# 2024-SS-ZT-2.net
KiCad netlist of a schematic drawn in EasyEDA Pro
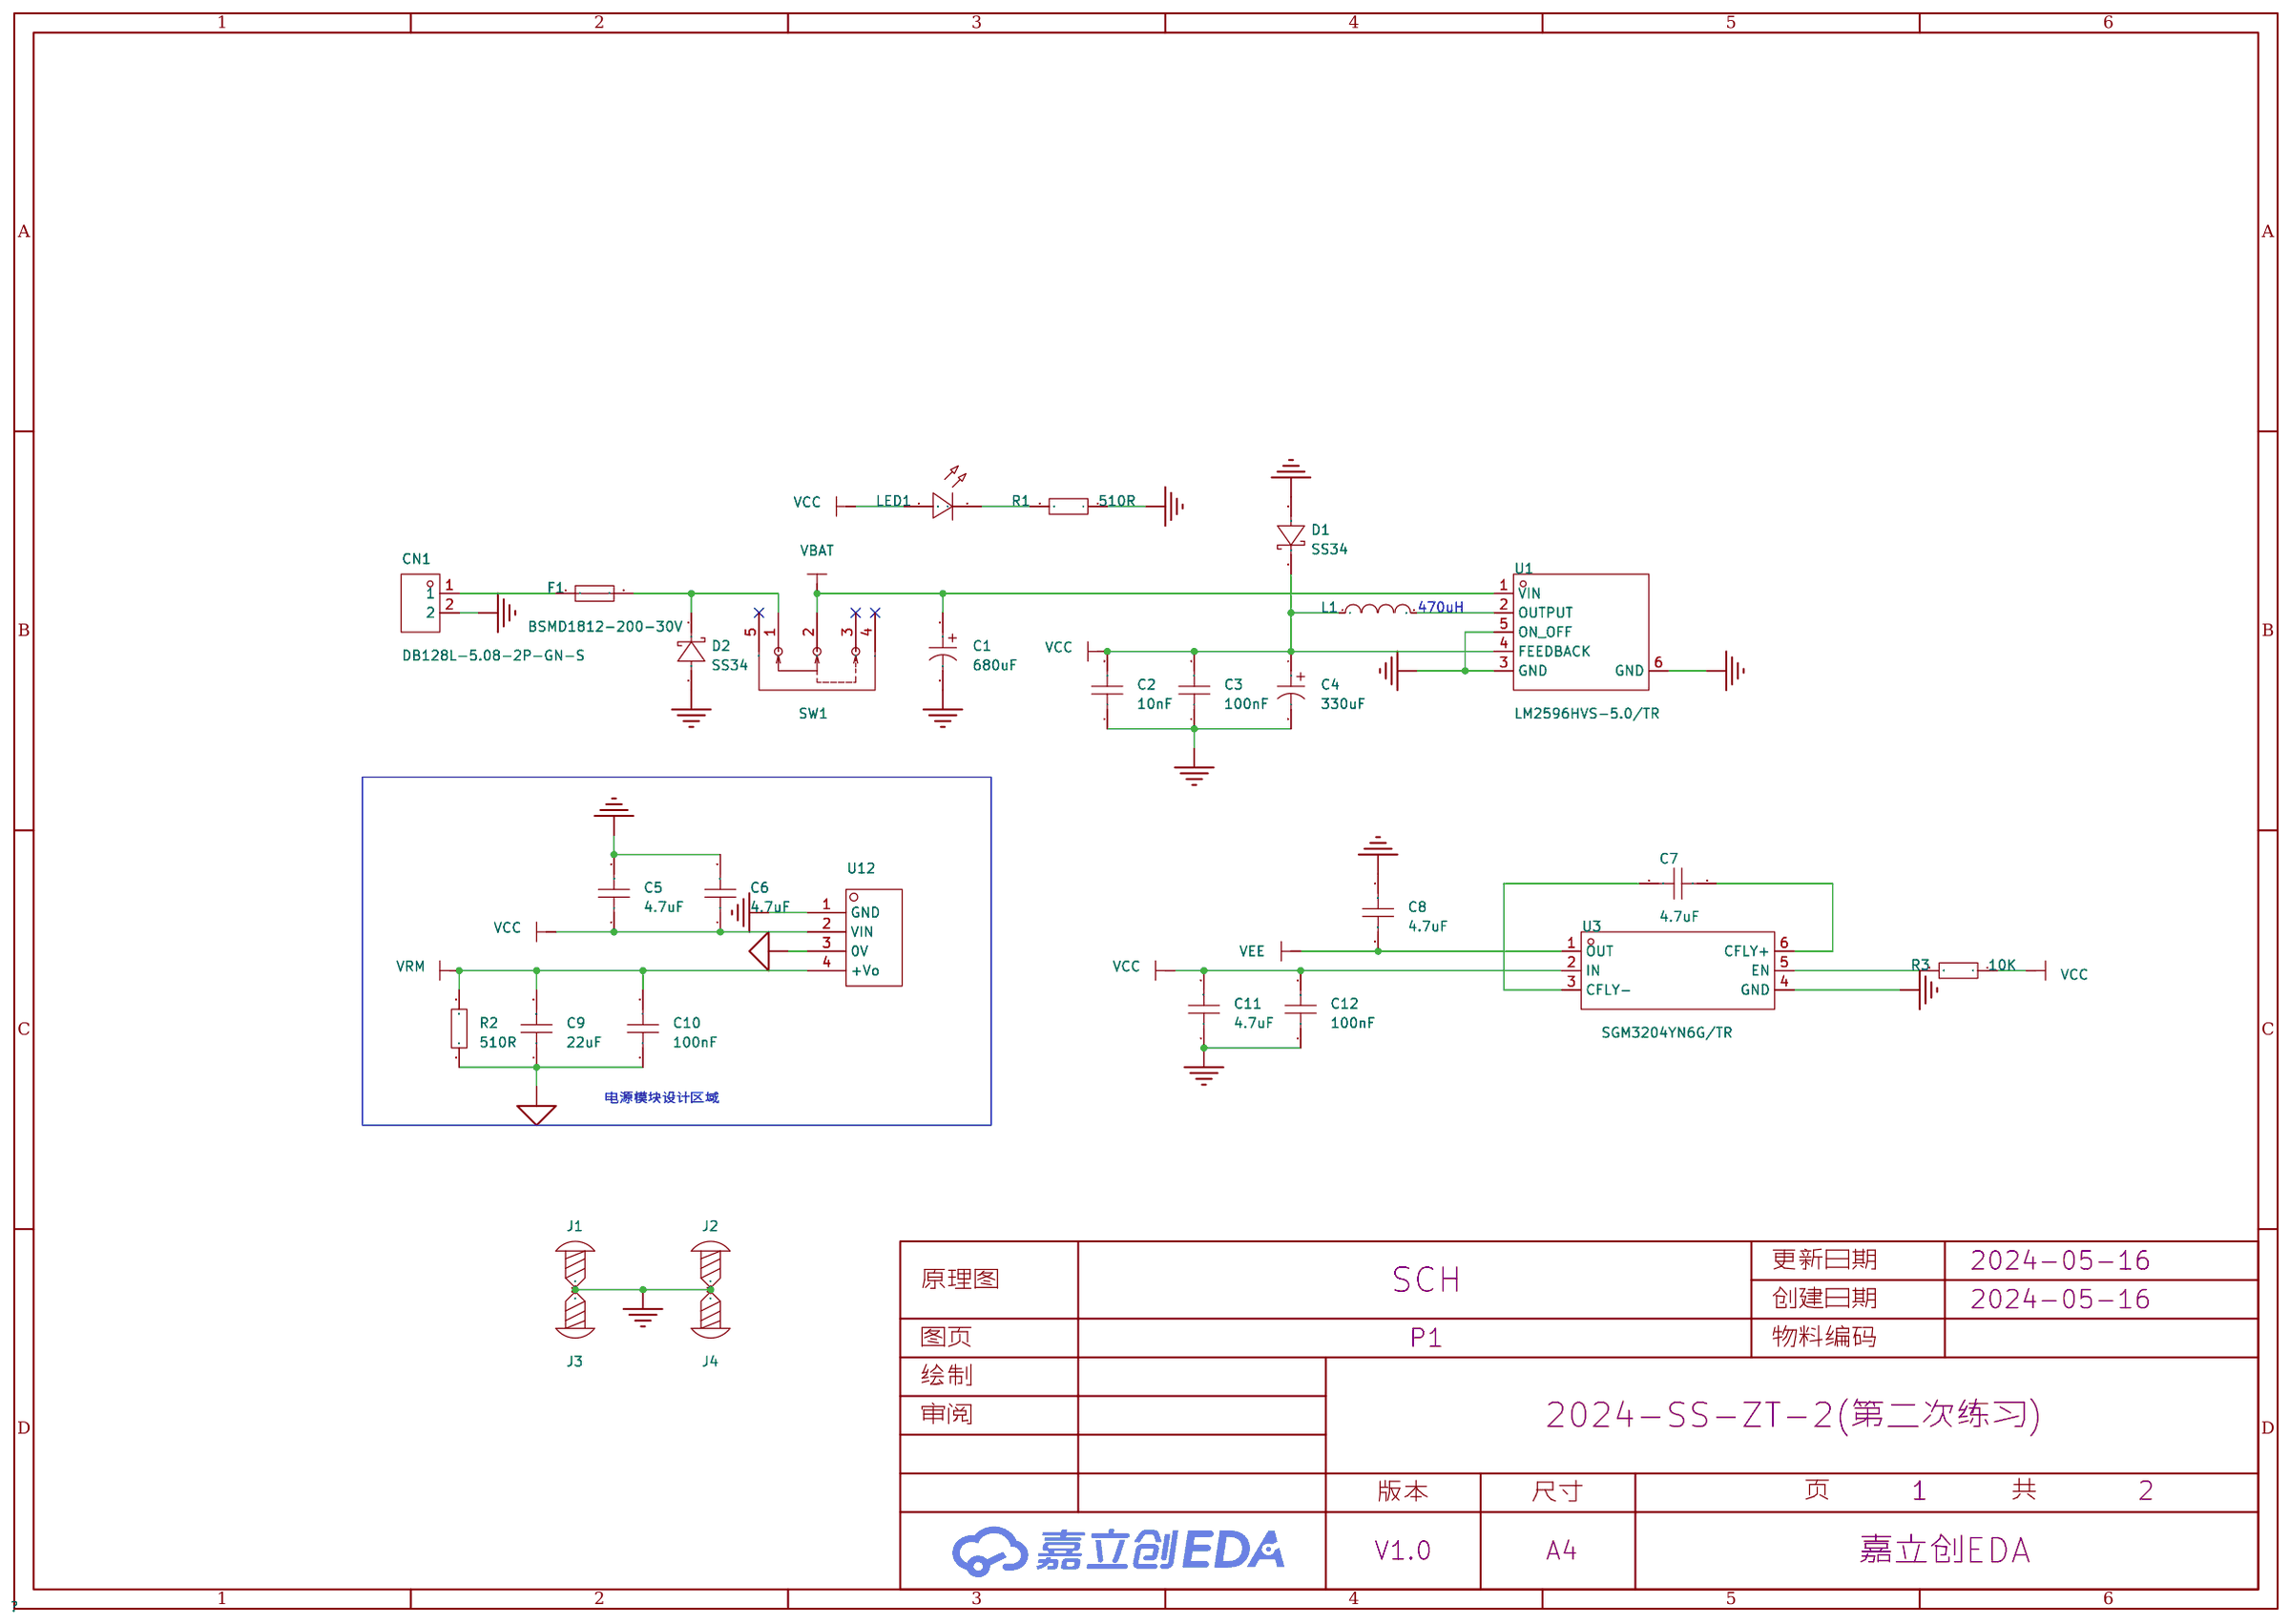
[diagram p0: P1]
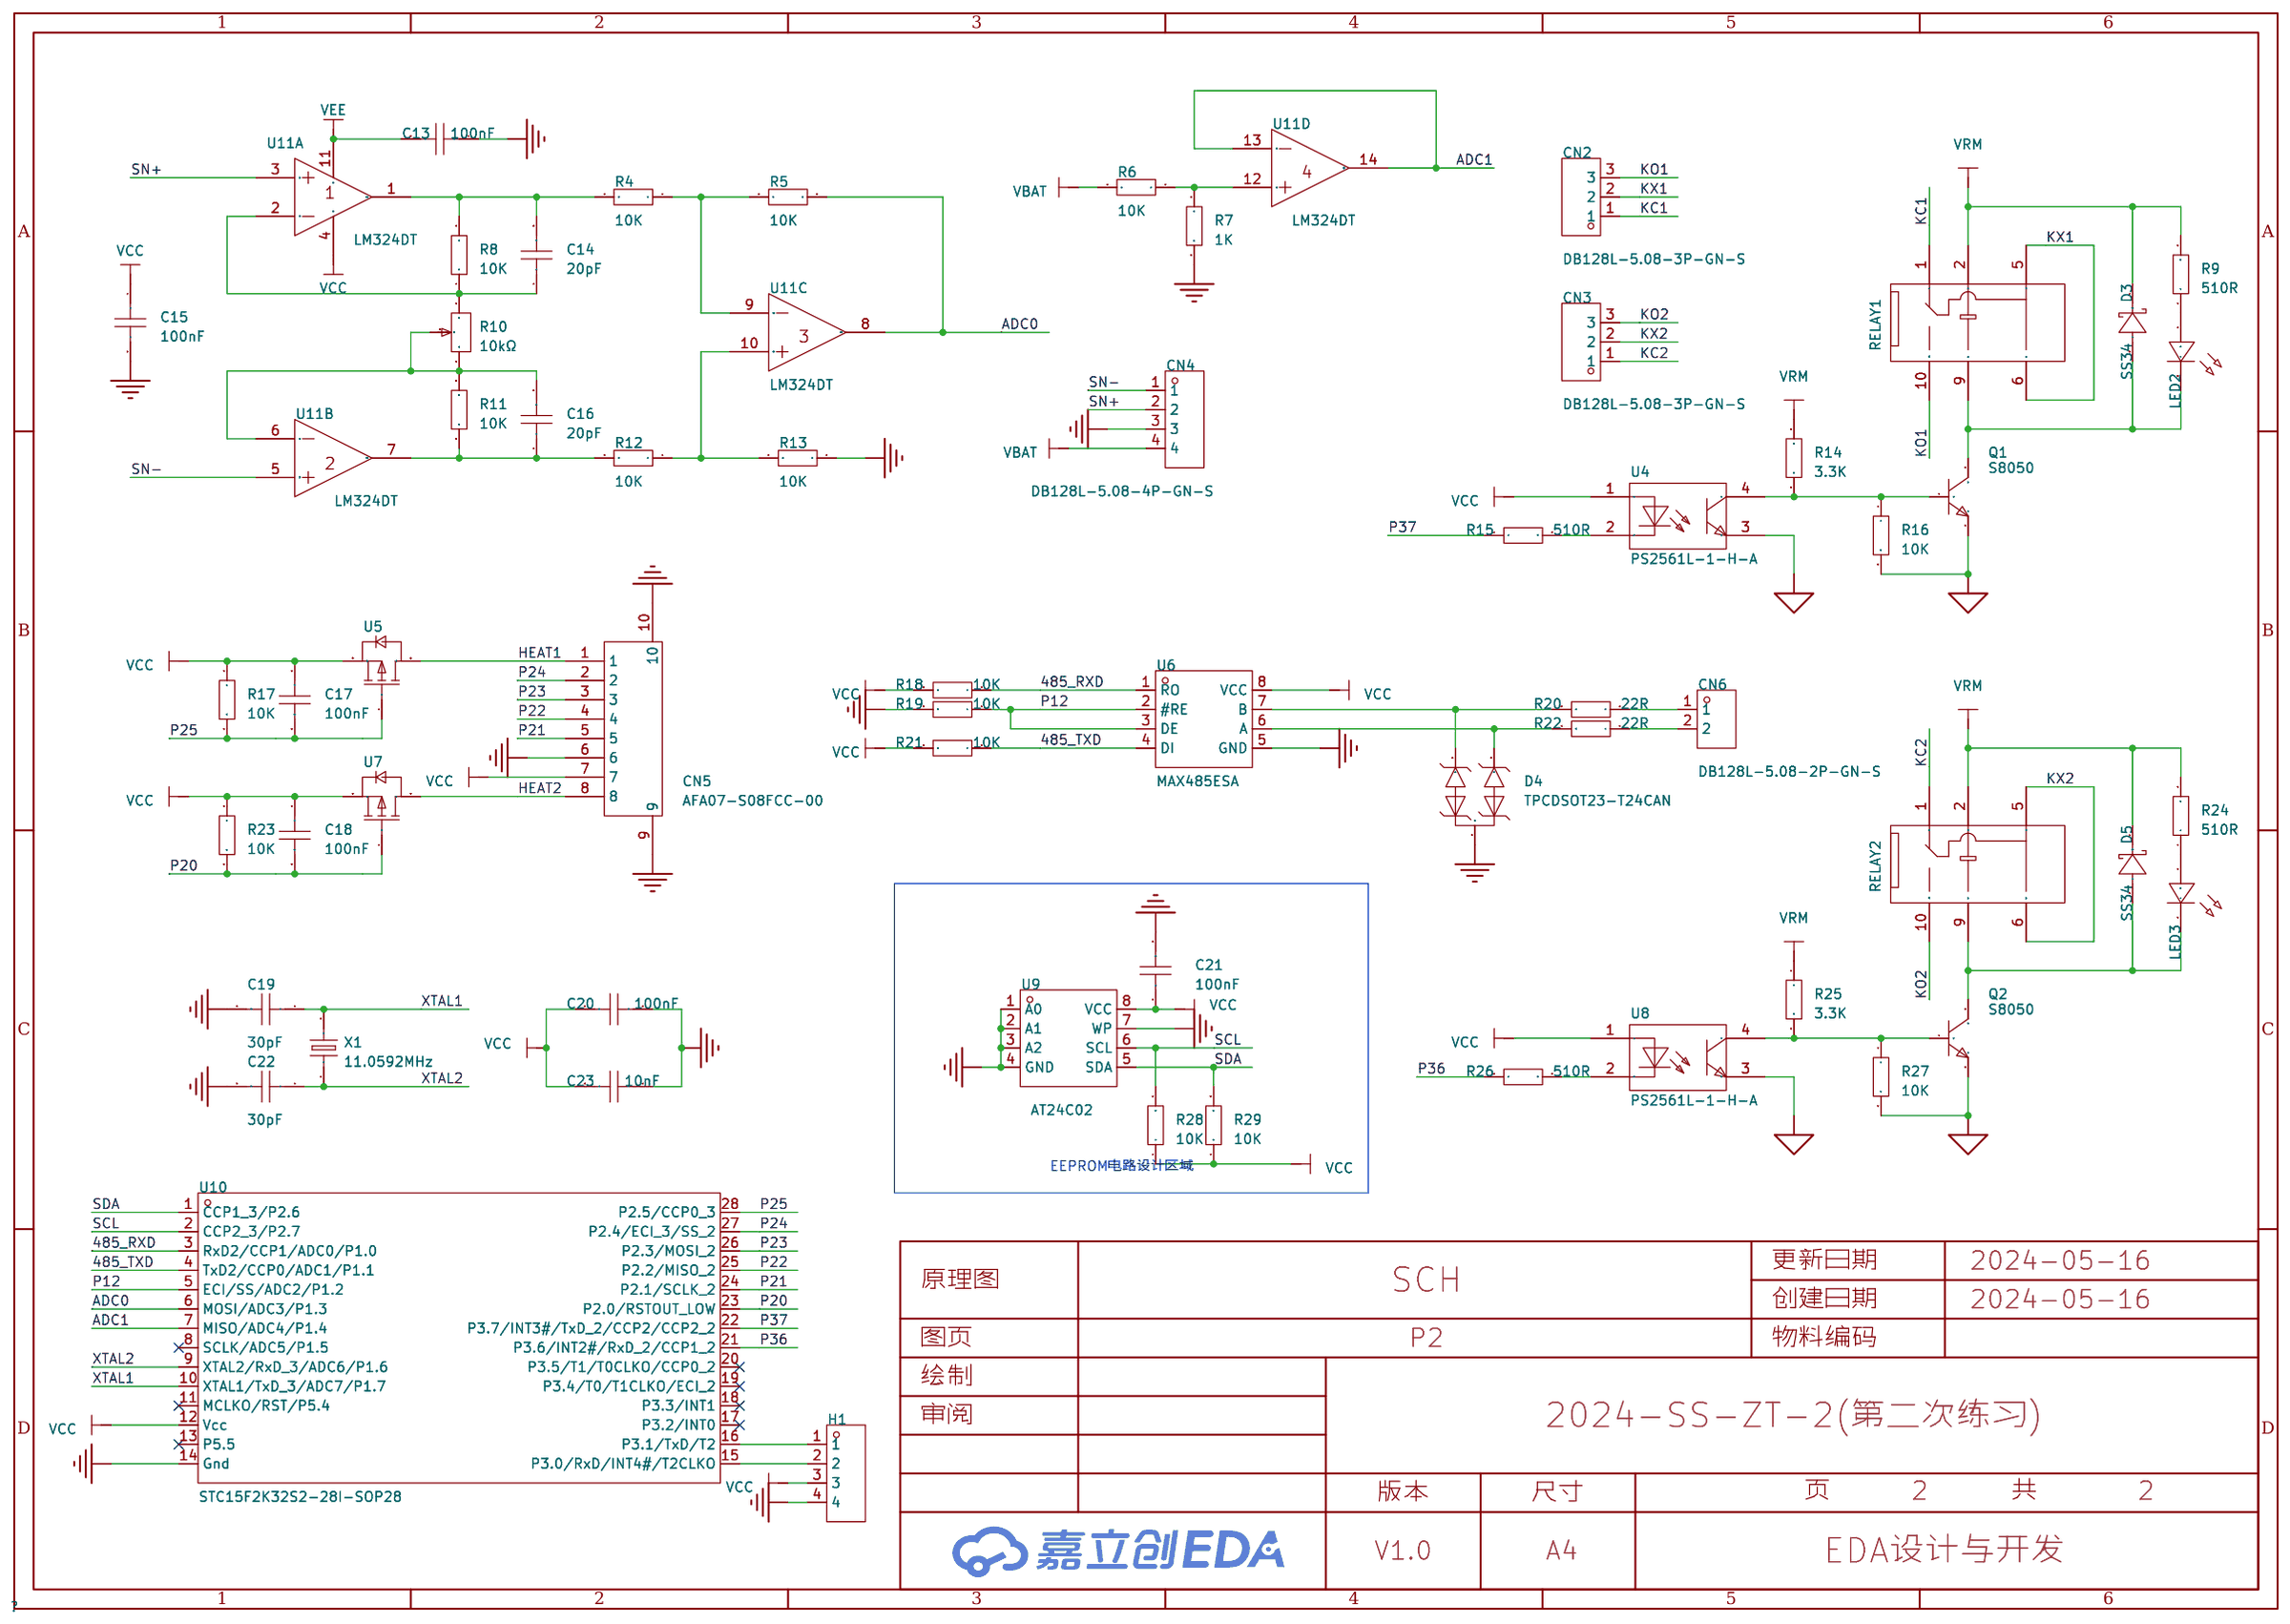
[diagram p1: P2]

(export (version "E")
  (design (tool "Eeschema 10.0.6"))
  (components
    (comp (ref "C1")
      (value "680uF")
      (footprint "easyedapro:CAP-SMD_BD10.0-L10.3-W10.3-LS11.3-FD")
      (description "容值:680uF;精度:±20%;额定电压:35V;纹波电流:380mA;")
      (fields (field (name "Manufacturer Part") "126RV0105") (field (name "Manufacturer") "KNSCHA(科尼盛)"))
      (libsource (lib "easyedapro") (part "126RV0105"))
    )
    (comp (ref "C2")
      (value "10nF")
      (footprint "easyedapro:C0805")
      (libsource (lib "easyedapro") (part "CapAcitance"))
    )
    (comp (ref "C3")
      (value "100nF")
      (footprint "easyedapro:C0805")
      (libsource (lib "easyedapro") (part "CapAcitance"))
    )
    (comp (ref "C4")
      (value "330uF")
      (footprint "easyedapro:CAP-SMD_BD6.3-L6.6-W6.6-LS7.6-RD")
      (description "容值:330uF;精度:±20%;额定电压:16V;纹波电流:170mA;")
      (fields (field (name "Manufacturer Part") "126RV0107") (field (name "Manufacturer") "KNSCHA(科尼盛)"))
      (libsource (lib "easyedapro") (part "126RV0107"))
    )
    (comp (ref "C5")
      (value "4.7uF")
      (footprint "easyedapro:C1206")
      (description "容值:22uF;精度:±10%;额定电压:16V;材质(温度系数):X5R;")
      (fields
        (field (name "Manufacturer Part") "CL31A226KOHNNNE")
        (field (name "Manufacturer") "SAMSUNG(三星)")
      )
      (libsource (lib "easyedapro") (part "CL31A226KOHNNNE"))
    )
    (comp (ref "C6")
      (value "4.7uF")
      (footprint "easyedapro:C1206")
      (description "容值:22uF;精度:±10%;额定电压:16V;材质(温度系数):X5R;")
      (fields
        (field (name "Manufacturer Part") "CL31A226KOHNNNE")
        (field (name "Manufacturer") "SAMSUNG(三星)")
      )
      (libsource (lib "easyedapro") (part "CL31A226KOHNNNE"))
    )
    (comp (ref "C7")
      (value "4.7uF")
      (footprint "easyedapro:C1206")
      (description "容值:22uF;精度:±10%;额定电压:16V;材质(温度系数):X5R;")
      (fields
        (field (name "Manufacturer Part") "CL31A226KOHNNNE")
        (field (name "Manufacturer") "SAMSUNG(三星)")
      )
      (libsource (lib "easyedapro") (part "CL31A226KOHNNNE"))
    )
    (comp (ref "C8")
      (value "4.7uF")
      (footprint "easyedapro:C1206")
      (description "容值:22uF;精度:±10%;额定电压:16V;材质(温度系数):X5R;")
      (fields
        (field (name "Manufacturer Part") "CL31A226KOHNNNE")
        (field (name "Manufacturer") "SAMSUNG(三星)")
      )
      (libsource (lib "easyedapro") (part "CL31A226KOHNNNE"))
    )
    (comp (ref "C9")
      (value "22uF")
      (footprint "easyedapro:C1206")
      (description "容值:22uF;精度:±10%;额定电压:16V;材质(温度系数):X5R;")
      (fields
        (field (name "Manufacturer Part") "CL31A226KOHNNNE")
        (field (name "Manufacturer") "SAMSUNG(三星)")
      )
      (libsource (lib "easyedapro") (part "CL31A226KOHNNNE"))
    )
    (comp (ref "C10")
      (value "100nF")
      (footprint "easyedapro:C0805")
      (libsource (lib "easyedapro") (part "CapAcitance"))
    )
    (comp (ref "C11")
      (value "4.7uF")
      (footprint "easyedapro:C1206")
      (description "容值:22uF;精度:±10%;额定电压:16V;材质(温度系数):X5R;")
      (fields
        (field (name "Manufacturer Part") "CL31A226KOHNNNE")
        (field (name "Manufacturer") "SAMSUNG(三星)")
      )
      (libsource (lib "easyedapro") (part "CL31A226KOHNNNE"))
    )
    (comp (ref "C12")
      (value "100nF")
      (footprint "easyedapro:C0805")
      (libsource (lib "easyedapro") (part "CapAcitance"))
    )
    (comp (ref "CN1")
      (value "DB128L-5.08-2P-GN-S")
      (footprint "easyedapro:CONN-TH_2P-P5.08_DB128L-5.08-2P")
      (fields (field (name "Manufacturer") "DORABO(地博电气)"))
      (libsource (lib "easyedapro") (part "DB128L-5.08-2P"))
    )
    (comp (ref "D1")
      (value "SS34")
      (footprint "easyedapro:SMA_L4.3-W2.5-LS5.0-RD")
      (description "二极管配置:独立式;正向压降(Vf):550mV@3A;直流反向耐压(Vr):40V;平均整流电流(Io):3A;")
      (fields (field (name "Manufacturer") "TWGMC(台湾迪嘉)"))
      (libsource (lib "easyedapro") (part "SS34_C727060"))
    )
    (comp (ref "D2")
      (value "SS34")
      (footprint "easyedapro:SMA_L4.3-W2.5-LS5.0-RD")
      (description "二极管配置:独立式;正向压降(Vf):550mV@3A;直流反向耐压(Vr):40V;平均整流电流(Io):3A;")
      (fields (field (name "Manufacturer") "TWGMC(台湾迪嘉)"))
      (libsource (lib "easyedapro") (part "SS34_C727060"))
    )
    (comp (ref "F1")
      (value "BSMD1812-200-30V")
      (footprint "easyedapro:F1812")
      (description "最大电压:30V;最大电流:40A;保持电流:2A;跳闸电流:4A;")
      (fields (field (name "Manufacturer") "BHFUSE(佰宏)"))
      (libsource (lib "easyedapro") (part "BSMD1812-200-30V"))
    )
    (comp (ref "J1") (value "~") (footprint "easyedapro:M2螺丝") (libsource (lib "easyedapro") (part "螺丝孔")))
    (comp (ref "J2") (value "~") (footprint "easyedapro:M2螺丝") (libsource (lib "easyedapro") (part "螺丝孔")))
    (comp (ref "J3") (value "~") (footprint "easyedapro:M2螺丝") (libsource (lib "easyedapro") (part "螺丝孔")))
    (comp (ref "J4") (value "~") (footprint "easyedapro:M2螺丝") (libsource (lib "easyedapro") (part "螺丝孔")))
    (comp (ref "L1")
      (value "470uH")
      (footprint "easyedapro:IND-SMD_L12.0-W12.0_YPRH120X")
      (description "电感值:470uH;精度:±20%;额定电流:1.06A;")
      (fields (field (name "Manufacturer Part") "YPRH1209-471M") (field (name "Manufacturer") "YJYCOIN(益嘉源)"))
      (libsource (lib "easyedapro") (part "YPRH1209-471M"))
    )
    (comp (ref "LED1")
      (value "~")
      (footprint "easyedapro:LED_TH-3mm")
      (libsource (lib "easyedapro") (part "LED_TH-R"))
    )
    (comp (ref "R1") (value "510R") (footprint "easyedapro:R0805") (libsource (lib "easyedapro") (part "电阻")))
    (comp (ref "R2") (value "510R") (footprint "easyedapro:R0805") (libsource (lib "easyedapro") (part "电阻")))
    (comp (ref "R3") (value "10K") (footprint "easyedapro:R0805") (libsource (lib "easyedapro") (part "电阻")))
    (comp (ref "SW1")
      (value "SK12D07VG4")
      (footprint "easyedapro:SW-TH_SK12D07VG4")
      (description "电路结构:单刀双掷;安装方式:侧插;额定电流(DC):500mA;额定电压(DC):50V;额定电流(AC):-;额定电压(AC):-;机械寿命:5千次;")
      (fields (field (name "Manufacturer") "SHOU HAN(首韩)"))
      (libsource (lib "easyedapro") (part "SK12D07VG4"))
    )
    (comp (ref "U1")
      (value "LM2596HVS-5.0/TR")
      (footprint "easyedapro:TO-263-5_L10.2-W8.9-P1.70-LS15.2-BR")
      (fields (field (name "Manufacturer") "HGSEMI(华冠)"))
      (libsource (lib "easyedapro") (part "LM2596HVS-5.0/TR"))
    )
    (comp (ref "U3")
      (value "SGM3204YN6G/TR")
      (footprint "easyedapro:SOT-23-6_L2.9-W1.6-P0.95-LS2.8-BR")
      (description "功能类型:-;输入电压:1.4V~5.5V;输出电压:-5.5V~-1.4V;输出电流(最大值):200mA;")
      (fields (field (name "Manufacturer") "SGMICRO(圣邦微)"))
      (libsource (lib "easyedapro") (part "SGM3204YN6G/TR"))
    )
    (comp (ref "U12")
      (value "~")
      (footprint "easyedapro:TH_PCON")
      (libsource (lib "easyedapro") (part "PCON"))
    )
    (comp (ref "C13")
      (value "100nF")
      (footprint "easyedapro:C0805")
      (libsource (lib "easyedapro") (part "CapAcitance"))
    )
    (comp (ref "C14")
      (value "20pF")
      (footprint "easyedapro:C0805")
      (libsource (lib "easyedapro") (part "CapAcitance"))
    )
    (comp (ref "C15")
      (value "100nF")
      (footprint "easyedapro:C0805")
      (libsource (lib "easyedapro") (part "CapAcitance"))
    )
    (comp (ref "C16")
      (value "20pF")
      (footprint "easyedapro:C0805")
      (libsource (lib "easyedapro") (part "CapAcitance"))
    )
    (comp (ref "C17")
      (value "100nF")
      (footprint "easyedapro:C0805")
      (libsource (lib "easyedapro") (part "CapAcitance"))
    )
    (comp (ref "C18")
      (value "100nF")
      (footprint "easyedapro:C0805")
      (libsource (lib "easyedapro") (part "CapAcitance"))
    )
    (comp (ref "C19")
      (value "30pF")
      (footprint "easyedapro:C0805")
      (libsource (lib "easyedapro") (part "CapAcitance"))
    )
    (comp (ref "C20")
      (value "100nF")
      (footprint "easyedapro:C0805")
      (libsource (lib "easyedapro") (part "CapAcitance"))
    )
    (comp (ref "C21")
      (value "100nF")
      (footprint "easyedapro:C0805")
      (libsource (lib "easyedapro") (part "CapAcitance"))
    )
    (comp (ref "C22")
      (value "30pF")
      (footprint "easyedapro:C0805")
      (libsource (lib "easyedapro") (part "CapAcitance"))
    )
    (comp (ref "C23")
      (value "10nF")
      (footprint "easyedapro:C0805")
      (libsource (lib "easyedapro") (part "CapAcitance"))
    )
    (comp (ref "CN2")
      (value "DB128L-5.08-3P-GN-S")
      (footprint "easyedapro:CONN-TH_DB128L-5.08-3P")
      (fields (field (name "Manufacturer") "DORABO(地博电气)"))
      (libsource (lib "easyedapro") (part "DB128L-5.08-3P"))
    )
    (comp (ref "CN3")
      (value "DB128L-5.08-3P-GN-S")
      (footprint "easyedapro:CONN-TH_DB128L-5.08-3P")
      (fields (field (name "Manufacturer") "DORABO(地博电气)"))
      (libsource (lib "easyedapro") (part "DB128L-5.08-3P"))
    )
    (comp (ref "CN4")
      (value "DB128L-5.08-4P-GN-S")
      (footprint "easyedapro:CONN-TH_4P_DB128L-5.08-4P-GN-S")
      (fields (field (name "Manufacturer") "DORABO(地博电气)"))
      (libsource (lib "easyedapro") (part "DB128L-5.08-4P-GN-S"))
    )
    (comp (ref "CN5")
      (value "AFA07-S08FCC-00")
      (footprint "easyedapro:FPC-SMD_P1.00-8P_LCS-XJ-H2.5")
      (description "锁定特性:抽屉式;触点类型:下接;触点数量:8P;间距:1mm;安装类型:卧贴;")
      (fields (field (name "Manufacturer") "JS(钜硕电子)"))
      (libsource (lib "easyedapro") (part "AFA07-S08FCC-00"))
    )
    (comp (ref "CN6")
      (value "DB128L-5.08-2P-GN-S")
      (footprint "easyedapro:CONN-TH_2P-P5.08_DB128L-5.08-2P")
      (fields (field (name "Manufacturer") "DORABO(地博电气)"))
      (libsource (lib "easyedapro") (part "DB128L-5.08-2P"))
    )
    (comp (ref "D3")
      (value "SS34")
      (footprint "easyedapro:SMA_L4.3-W2.5-LS5.0-RD")
      (description "二极管配置:独立式;正向压降(Vf):550mV@3A;直流反向耐压(Vr):40V;平均整流电流(Io):3A;")
      (fields (field (name "Manufacturer") "TWGMC(台湾迪嘉)"))
      (libsource (lib "easyedapro") (part "SS34_C727060"))
    )
    (comp (ref "D4")
      (value "TPCDSOT23-T24CAN")
      (footprint "easyedapro:SOT-23-3_L2.9-W1.3-P1.90-LS2.4-BR")
      (fields (field (name "Manufacturer") "TECH PUBLIC(台舟)"))
      (libsource (lib "easyedapro") (part "TPCDSOT23-T24CAN"))
    )
    (comp (ref "D5")
      (value "SS34")
      (footprint "easyedapro:SMA_L4.3-W2.5-LS5.0-RD")
      (description "二极管配置:独立式;正向压降(Vf):550mV@3A;直流反向耐压(Vr):40V;平均整流电流(Io):3A;")
      (fields (field (name "Manufacturer") "TWGMC(台湾迪嘉)"))
      (libsource (lib "easyedapro") (part "SS34_C727060"))
    )
    (comp (ref "H1")
      (value "~")
      (footprint "easyedapro:HDR-TH_4P-P2.54-V-F")
      (libsource (lib "easyedapro") (part "2.54-1*4P母"))
    )
    (comp (ref "LED2")
      (value "~")
      (footprint "easyedapro:LED_TH-3mm")
      (libsource (lib "easyedapro") (part "LED_TH-G"))
    )
    (comp (ref "LED3")
      (value "~")
      (footprint "easyedapro:LED_TH-3mm")
      (libsource (lib "easyedapro") (part "LED_TH-G"))
    )
    (comp (ref "Q1")
      (value "S8050")
      (footprint "easyedapro:SOT-23-3_L2.9-W1.3-P1.90-LS2.4-BR")
      (description "晶体管类型:NPN;集电极电流(Ic):500mA;集射极击穿电压(Vceo):25V;功率(Pd):300mW;")
      (fields (field (name "Manufacturer") "YONGYUTAI(永裕泰)"))
      (libsource (lib "easyedapro") (part "S8050_C2891804"))
    )
    (comp (ref "Q2")
      (value "S8050")
      (footprint "easyedapro:SOT-23-3_L2.9-W1.3-P1.90-LS2.4-BR")
      (description "晶体管类型:NPN;集电极电流(Ic):500mA;集射极击穿电压(Vceo):25V;功率(Pd):300mW;")
      (fields (field (name "Manufacturer") "YONGYUTAI(永裕泰)"))
      (libsource (lib "easyedapro") (part "S8050_C2891804"))
    )
    (comp (ref "R4") (value "10K") (footprint "easyedapro:R0805") (libsource (lib "easyedapro") (part "电阻")))
    (comp (ref "R5") (value "10K") (footprint "easyedapro:R0805") (libsource (lib "easyedapro") (part "电阻")))
    (comp (ref "R6") (value "10K") (footprint "easyedapro:R0805") (libsource (lib "easyedapro") (part "电阻")))
    (comp (ref "R7") (value "1K") (footprint "easyedapro:R0805") (libsource (lib "easyedapro") (part "电阻")))
    (comp (ref "R8") (value "10K") (footprint "easyedapro:R0805") (libsource (lib "easyedapro") (part "电阻")))
    (comp (ref "R9") (value "510R") (footprint "easyedapro:R0805") (libsource (lib "easyedapro") (part "电阻")))
    (comp (ref "R10")
      (value "10kΩ")
      (footprint "easyedapro:RES-ADJ-TH_3P-L10.0-W10.0-P2.50-BL-BS")
      (description "阻值:20kΩ;精度:±10%;功率:500mW;温度系数:±100ppm/°C;")
      (fields (field (name "Manufacturer Part") "3296W-1-203LF") (field (name "Manufacturer") "BOURNS"))
      (libsource (lib "easyedapro") (part "3296W-1-203LF"))
    )
    (comp (ref "R11") (value "10K") (footprint "easyedapro:R0805") (libsource (lib "easyedapro") (part "电阻")))
    (comp (ref "R12") (value "10K") (footprint "easyedapro:R0805") (libsource (lib "easyedapro") (part "电阻")))
    (comp (ref "R13") (value "10K") (footprint "easyedapro:R0805") (libsource (lib "easyedapro") (part "电阻")))
    (comp (ref "R14")
      (value "3.3K")
      (footprint "easyedapro:R0805")
      (libsource (lib "easyedapro") (part "电阻"))
    )
    (comp (ref "R15")
      (value "510R")
      (footprint "easyedapro:R0805")
      (libsource (lib "easyedapro") (part "电阻"))
    )
    (comp (ref "R16") (value "10K") (footprint "easyedapro:R0805") (libsource (lib "easyedapro") (part "电阻")))
    (comp (ref "R17") (value "10K") (footprint "easyedapro:R0805") (libsource (lib "easyedapro") (part "电阻")))
    (comp (ref "R18") (value "10K") (footprint "easyedapro:R0805") (libsource (lib "easyedapro") (part "电阻")))
    (comp (ref "R19") (value "10K") (footprint "easyedapro:R0805") (libsource (lib "easyedapro") (part "电阻")))
    (comp (ref "R20") (value "22R") (footprint "easyedapro:R0805") (libsource (lib "easyedapro") (part "电阻")))
    (comp (ref "R21") (value "10K") (footprint "easyedapro:R0805") (libsource (lib "easyedapro") (part "电阻")))
    (comp (ref "R22") (value "22R") (footprint "easyedapro:R0805") (libsource (lib "easyedapro") (part "电阻")))
    (comp (ref "R23") (value "10K") (footprint "easyedapro:R0805") (libsource (lib "easyedapro") (part "电阻")))
    (comp (ref "R24")
      (value "510R")
      (footprint "easyedapro:R0805")
      (libsource (lib "easyedapro") (part "电阻"))
    )
    (comp (ref "R25")
      (value "3.3K")
      (footprint "easyedapro:R0805")
      (libsource (lib "easyedapro") (part "电阻"))
    )
    (comp (ref "R26")
      (value "510R")
      (footprint "easyedapro:R0805")
      (libsource (lib "easyedapro") (part "电阻"))
    )
    (comp (ref "R27") (value "10K") (footprint "easyedapro:R0805") (libsource (lib "easyedapro") (part "电阻")))
    (comp (ref "R28") (value "10K") (footprint "easyedapro:R0805") (libsource (lib "easyedapro") (part "电阻")))
    (comp (ref "R29") (value "10K") (footprint "easyedapro:R0805") (libsource (lib "easyedapro") (part "电阻")))
    (comp (ref "RELAY1")
      (value "G5V-1 DC5")
      (footprint "easyedapro:RELAY-TH_G5V-1")
      (description "线圈电压:5V;触点形式:一组转换:1C(单刀双掷-转换);触点容量(电阻负载):-;最大切换电压:125V@AC；60V@DC;最大切换电流:1A;")
      (fields (field (name "Manufacturer") "OMRON(欧姆龙)"))
      (libsource (lib "easyedapro") (part "G5V-1-5VDC"))
    )
    (comp (ref "RELAY2")
      (value "G5V-1 DC5")
      (footprint "easyedapro:RELAY-TH_G5V-1")
      (description "线圈电压:5V;触点形式:一组转换:1C(单刀双掷-转换);触点容量(电阻负载):-;最大切换电压:125V@AC；60V@DC;最大切换电流:1A;")
      (fields (field (name "Manufacturer") "OMRON(欧姆龙)"))
      (libsource (lib "easyedapro") (part "G5V-1-5VDC"))
    )
    (comp (ref "U4")
      (value "PS2561L-1-H-A")
      (footprint "easyedapro:SOP-4_L6.5-W4.6-P2.54-LS9.6-TL")
      (fields (field (name "Manufacturer") "California Eastern Laboratories"))
      (libsource (lib "easyedapro") (part "PS2561L-1-H-A"))
    )
    (comp (ref "U5")
      (value "SI2301-ZE")
      (footprint "easyedapro:SOT-23-3_L2.9-W1.3-P1.90-LS2.4-BR")
      (fields (field (name "Manufacturer") "HXY MOSFET(华轩阳电子)"))
      (libsource (lib "easyedapro") (part "SI2301-ZE"))
    )
    (comp (ref "U6")
      (value "MAX485ESA")
      (footprint "easyedapro:SOP-8_L5.0-W4.0-P1.27-LS6.0-BL")
      (fields (field (name "Manufacturer") "UMW(友台半导体)"))
      (libsource (lib "easyedapro") (part "MAX485EAS"))
    )
    (comp (ref "U7")
      (value "SI2301-ZE")
      (footprint "easyedapro:SOT-23-3_L2.9-W1.3-P1.90-LS2.4-BR")
      (fields (field (name "Manufacturer") "HXY MOSFET(华轩阳电子)"))
      (libsource (lib "easyedapro") (part "SI2301-ZE"))
    )
    (comp (ref "U8")
      (value "PS2561L-1-H-A")
      (footprint "easyedapro:SOP-4_L6.5-W4.6-P2.54-LS9.6-TL")
      (fields (field (name "Manufacturer") "California Eastern Laboratories"))
      (libsource (lib "easyedapro") (part "PS2561L-1-H-A"))
    )
    (comp (ref "U9")
      (value "AT24C02")
      (footprint "easyedapro:SOP-8_L4.9-W3.9-P1.27-LS6.0-BL")
      (description "接口类型:I2C;存储容量:2Kbit;时钟频率(fc):400kHz~1MHz;")
      (fields (field (name "Manufacturer") "HXY MOSFET(华轩阳电子)"))
      (libsource (lib "easyedapro") (part "AT24C02_C7470930"))
    )
    (comp (ref "U10")
      (value "STC15F2K32S2-28I-SOP28")
      (footprint "easyedapro:SOP-28_L17.9-W7.5-P1.27-LS10.3-BL")
      (fields (field (name "Manufacturer") "STC(宏晶)"))
      (libsource (lib "easyedapro") (part "STC15F2K32S2-28I-SOP28"))
    )
    (comp (ref "U11")
      (value "LM324DT")
      (footprint "easyedapro:SOIC-14_L8.7-W3.9-P1.27-LS6.0-BL")
      (description "放大器数:四路;增益带宽积(GBP):1.3MHz;输入偏置电流(Ib):20nA;压摆率(SR):0.4V/us;带宽(-3db):-;")
      (fields (field (name "Manufacturer") "ST(意法半导体)"))
      (libsource (lib "easyedapro") (part "LM324DT"))
    )
    (comp (ref "X1")
      (value "11.0592MHz")
      (footprint "easyedapro:HC-49US_L11.5-W4.5-P4.88")
      (description "晶振类型:直插晶振;频率:11.0592MHz;常温频差:±30ppm;外接负载电容:20pF;频率稳定度(全温):±30ppm;")
      (fields
        (field (name "Manufacturer Part") "TAXD11.0592M2GLFBET2T")
        (field (name "Manufacturer") "YJX(雅晶鑫)")
      )
      (libsource (lib "easyedapro") (part "HC-49S11.0592MHZ20PF30PPM"))
    )
  )
  (nets
    (net (code "1") (name "0") (class "Default")
      (node (ref "C10") (pin "1") (pinfunction "1_1") (pintype "input"))
      (node (ref "C9") (pin "1") (pinfunction "1_1") (pintype "unspecified"))
      (node (ref "Q1") (pin "2") (pinfunction "E_2") (pintype "unspecified"))
      (node (ref "Q2") (pin "2") (pinfunction "E_2") (pintype "unspecified"))
      (node (ref "R16") (pin "2") (pinfunction "2_2") (pintype "input"))
      (node (ref "R2") (pin "1") (pinfunction "1_1") (pintype "input"))
      (node (ref "R27") (pin "2") (pinfunction "2_2") (pintype "input"))
      (node (ref "U12") (pin "3") (pinfunction "0V_3") (pintype "input"))
      (node (ref "U4") (pin "3") (pinfunction "3_3") (pintype "input"))
      (node (ref "U8") (pin "3") (pinfunction "3_3") (pintype "input"))
    )
    (net (code "2") (name "485_RXD") (class "Default")
      (node (ref "R18") (pin "1") (pinfunction "1_1") (pintype "input"))
      (node (ref "U10") (pin "3") (pinfunction "RxD2/CCP1/ADC0/P1.0_3") (pintype "input"))
      (node (ref "U6") (pin "1") (pinfunction "RO_1") (pintype "unspecified"))
    )
    (net (code "3") (name "485_TXD") (class "Default")
      (node (ref "R21") (pin "1") (pinfunction "1_1") (pintype "input"))
      (node (ref "U10") (pin "4") (pinfunction "TxD2/CCP0/ADC1/P1.1_4") (pintype "input"))
      (node (ref "U6") (pin "4") (pinfunction "DI_4") (pintype "unspecified"))
    )
    (net (code "4") (name "ADC0") (class "Default")
      (node (ref "R5") (pin "1") (pinfunction "1_1") (pintype "input"))
      (node (ref "U10") (pin "6") (pinfunction "MOSI/ADC3/P1.3_6") (pintype "input"))
      (node (ref "U11") (pin "8") (pinfunction "OUT3_8") (pintype "unspecified"))
    )
    (net (code "5") (name "ADC1") (class "Default")
      (node (ref "U10") (pin "7") (pinfunction "MISO/ADC4/P1.4_7") (pintype "input"))
      (node (ref "U11") (pin "13") (pinfunction "IN4-_13") (pintype "unspecified"))
      (node (ref "U11") (pin "14") (pinfunction "OUT4_14") (pintype "unspecified"))
    )
    (net (code "6") (name "GND") (class "Default")
      (node (ref "C1") (pin "2") (pinfunction "2_2") (pintype "input"))
      (node (ref "C11") (pin "1") (pinfunction "1_1") (pintype "unspecified"))
      (node (ref "C12") (pin "1") (pinfunction "1_1") (pintype "input"))
      (node (ref "C13") (pin "1") (pinfunction "1_1") (pintype "input"))
      (node (ref "C15") (pin "2") (pinfunction "2_2") (pintype "input"))
      (node (ref "C19") (pin "2") (pinfunction "2_2") (pintype "input"))
      (node (ref "C2") (pin "1") (pinfunction "1_1") (pintype "input"))
      (node (ref "C20") (pin "1") (pinfunction "1_1") (pintype "input"))
      (node (ref "C21") (pin "2") (pinfunction "2_2") (pintype "input"))
      (node (ref "C22") (pin "2") (pinfunction "2_2") (pintype "input"))
      (node (ref "C23") (pin "1") (pinfunction "1_1") (pintype "input"))
      (node (ref "C3") (pin "1") (pinfunction "1_1") (pintype "input"))
      (node (ref "C4") (pin "2") (pinfunction "2_2") (pintype "input"))
      (node (ref "C5") (pin "2") (pinfunction "2_2") (pintype "unspecified"))
      (node (ref "C6") (pin "2") (pinfunction "2_2") (pintype "unspecified"))
      (node (ref "C8") (pin "1") (pinfunction "1_1") (pintype "unspecified"))
      (node (ref "CN1") (pin "2") (pinfunction "2_2") (pintype "unspecified"))
      (node (ref "CN4") (pin "3") (pinfunction "3_3") (pintype "unspecified"))
      (node (ref "CN5") (pin "10") (pinfunction "10_10") (pintype "unspecified"))
      (node (ref "CN5") (pin "6") (pinfunction "6_6") (pintype "unspecified"))
      (node (ref "CN5") (pin "9") (pinfunction "9_9") (pintype "unspecified"))
      (node (ref "D1") (pin "2") (pinfunction "A_2") (pintype "unspecified"))
      (node (ref "D2") (pin "2") (pinfunction "A_2") (pintype "unspecified"))
      (node (ref "D4") (pin "3") (pinfunction "3_3") (pintype "unspecified"))
      (node (ref "H1") (pin "4") (pinfunction "4_4") (pintype "unspecified"))
      (node (ref "J1") (pin "1") (pinfunction "1_1") (pintype "input"))
      (node (ref "J2") (pin "1") (pinfunction "1_1") (pintype "input"))
      (node (ref "J3") (pin "1") (pinfunction "1_1") (pintype "input"))
      (node (ref "J4") (pin "1") (pinfunction "1_1") (pintype "input"))
      (node (ref "R1") (pin "1") (pinfunction "1_1") (pintype "input"))
      (node (ref "R13") (pin "1") (pinfunction "1_1") (pintype "input"))
      (node (ref "R19") (pin "2") (pinfunction "2_2") (pintype "input"))
      (node (ref "R7") (pin "2") (pinfunction "2_2") (pintype "input"))
      (node (ref "U1") (pin "3") (pinfunction "GND_3") (pintype "input"))
      (node (ref "U1") (pin "5") (pinfunction "ON_OFF_5") (pintype "input"))
      (node (ref "U1") (pin "6") (pinfunction "GND_6") (pintype "input"))
      (node (ref "U10") (pin "14") (pinfunction "Gnd_14") (pintype "input"))
      (node (ref "U12") (pin "1") (pinfunction "GND_1") (pintype "input"))
      (node (ref "U3") (pin "4") (pinfunction "GND_4") (pintype "unspecified"))
      (node (ref "U6") (pin "5") (pinfunction "GND_5") (pintype "unspecified"))
      (node (ref "U9") (pin "1") (pinfunction "A0_1") (pintype "unspecified"))
      (node (ref "U9") (pin "2") (pinfunction "A1_2") (pintype "unspecified"))
      (node (ref "U9") (pin "3") (pinfunction "A2_3") (pintype "unspecified"))
      (node (ref "U9") (pin "4") (pinfunction "GND_4") (pintype "unspecified"))
      (node (ref "U9") (pin "7") (pinfunction "WP_7") (pintype "unspecified"))
    )
    (net (code "7") (name "HEAT1") (class "Default")
      (node (ref "CN5") (pin "1") (pinfunction "1_1") (pintype "unspecified"))
      (node (ref "U5") (pin "3") (pinfunction "D_3") (pintype "unspecified"))
    )
    (net (code "8") (name "HEAT2") (class "Default")
      (node (ref "CN5") (pin "8") (pinfunction "8_8") (pintype "unspecified"))
      (node (ref "U7") (pin "3") (pinfunction "D_3") (pintype "unspecified"))
    )
    (net (code "9") (name "KC1") (class "Default")
      (node (ref "CN2") (pin "1") (pinfunction "1_1") (pintype "unspecified"))
      (node (ref "RELAY1") (pin "1") (pinfunction "1_1") (pintype "input"))
    )
    (net (code "10") (name "KC2") (class "Default")
      (node (ref "CN3") (pin "1") (pinfunction "1_1") (pintype "unspecified"))
      (node (ref "RELAY2") (pin "1") (pinfunction "1_1") (pintype "input"))
    )
    (net (code "11") (name "KO1") (class "Default")
      (node (ref "CN2") (pin "3") (pinfunction "3_3") (pintype "unspecified"))
      (node (ref "RELAY1") (pin "10") (pinfunction "10_10") (pintype "input"))
    )
    (net (code "12") (name "KO2") (class "Default")
      (node (ref "CN3") (pin "3") (pinfunction "3_3") (pintype "unspecified"))
      (node (ref "RELAY2") (pin "10") (pinfunction "10_10") (pintype "input"))
    )
    (net (code "13") (name "KX1") (class "Default")
      (node (ref "CN2") (pin "2") (pinfunction "2_2") (pintype "unspecified"))
      (node (ref "RELAY1") (pin "5") (pinfunction "5_5") (pintype "input"))
      (node (ref "RELAY1") (pin "6") (pinfunction "6_6") (pintype "input"))
    )
    (net (code "14") (name "KX2") (class "Default")
      (node (ref "CN3") (pin "2") (pinfunction "2_2") (pintype "unspecified"))
      (node (ref "RELAY2") (pin "5") (pinfunction "5_5") (pintype "input"))
      (node (ref "RELAY2") (pin "6") (pinfunction "6_6") (pintype "input"))
    )
    (net (code "15") (name "Net-(CN1-Pad1)") (class "Default")
      (node (ref "CN1") (pin "1") (pinfunction "1_1") (pintype "unspecified"))
      (node (ref "F1") (pin "1") (pinfunction "1_1") (pintype "unspecified"))
    )
    (net (code "16") (name "Net-(CN6-Pad1)") (class "Default")
      (node (ref "CN6") (pin "1") (pinfunction "1_1") (pintype "unspecified"))
      (node (ref "R20") (pin "1") (pinfunction "1_1") (pintype "input"))
    )
    (net (code "17") (name "Net-(CN6-Pad2)") (class "Default")
      (node (ref "CN6") (pin "2") (pinfunction "2_2") (pintype "unspecified"))
      (node (ref "R22") (pin "1") (pinfunction "1_1") (pintype "input"))
    )
    (net (code "18") (name "Net-(D2-C)") (class "Default")
      (node (ref "D2") (pin "1") (pinfunction "C_1") (pintype "unspecified"))
      (node (ref "F1") (pin "2") (pinfunction "2_2") (pintype "unspecified"))
      (node (ref "SW1") (pin "1") (pinfunction "1_1") (pintype "unspecified"))
    )
    (net (code "19") (name "Net-(D3-A)") (class "Default")
      (node (ref "D3") (pin "2") (pinfunction "A_2") (pintype "unspecified"))
      (node (ref "LED2") (pin "2") (pinfunction "A_2") (pintype "input"))
      (node (ref "Q1") (pin "3") (pinfunction "C_3") (pintype "unspecified"))
      (node (ref "RELAY1") (pin "9") (pinfunction "9_9") (pintype "input"))
    )
    (net (code "20") (name "Net-(D5-A)") (class "Default")
      (node (ref "D5") (pin "2") (pinfunction "A_2") (pintype "unspecified"))
      (node (ref "LED3") (pin "2") (pinfunction "A_2") (pintype "input"))
      (node (ref "Q2") (pin "3") (pinfunction "C_3") (pintype "unspecified"))
      (node (ref "RELAY2") (pin "9") (pinfunction "9_9") (pintype "input"))
    )
    (net (code "21") (name "Net-(LED1-A)") (class "Default")
      (node (ref "LED1") (pin "2") (pinfunction "A_2") (pintype "input"))
      (node (ref "R1") (pin "2") (pinfunction "2_2") (pintype "input"))
    )
    (net (code "22") (name "Net-(LED2-C)") (class "Default")
      (node (ref "LED2") (pin "1") (pinfunction "C_1") (pintype "input"))
      (node (ref "R9") (pin "1") (pinfunction "1_1") (pintype "input"))
    )
    (net (code "23") (name "Net-(LED3-C)") (class "Default")
      (node (ref "LED3") (pin "1") (pinfunction "C_1") (pintype "input"))
      (node (ref "R24") (pin "1") (pinfunction "1_1") (pintype "input"))
    )
    (net (code "24") (name "Net-(Q1-B)") (class "Default")
      (node (ref "Q1") (pin "1") (pinfunction "B_1") (pintype "unspecified"))
      (node (ref "R14") (pin "2") (pinfunction "2_2") (pintype "input"))
      (node (ref "R16") (pin "1") (pinfunction "1_1") (pintype "input"))
      (node (ref "U4") (pin "4") (pinfunction "4_4") (pintype "input"))
    )
    (net (code "25") (name "Net-(Q2-B)") (class "Default")
      (node (ref "Q2") (pin "1") (pinfunction "B_1") (pintype "unspecified"))
      (node (ref "R25") (pin "2") (pinfunction "2_2") (pintype "input"))
      (node (ref "R27") (pin "1") (pinfunction "1_1") (pintype "input"))
      (node (ref "U8") (pin "4") (pinfunction "4_4") (pintype "input"))
    )
    (net (code "26") (name "Net-(R15-Pad2)") (class "Default")
      (node (ref "R15") (pin "2") (pinfunction "2_2") (pintype "input"))
      (node (ref "U4") (pin "2") (pinfunction "2_2") (pintype "input"))
    )
    (net (code "27") (name "Net-(R26-Pad2)") (class "Default")
      (node (ref "R26") (pin "2") (pinfunction "2_2") (pintype "input"))
      (node (ref "U8") (pin "2") (pinfunction "2_2") (pintype "input"))
    )
    (net (code "28") (name "Net-(U1-OUTPUT)") (class "Default")
      (node (ref "L1") (pin "2") (pinfunction "2_2") (pintype "unspecified"))
      (node (ref "U1") (pin "2") (pinfunction "OUTPUT_2") (pintype "input"))
    )
    (net (code "29") (name "Net-(U3-CFLY+)") (class "Default")
      (node (ref "C7") (pin "2") (pinfunction "2_2") (pintype "unspecified"))
      (node (ref "U3") (pin "6") (pinfunction "CFLY+_6") (pintype "unspecified"))
    )
    (net (code "30") (name "Net-(U3-CFLY-)") (class "Default")
      (node (ref "C7") (pin "1") (pinfunction "1_1") (pintype "unspecified"))
      (node (ref "U3") (pin "3") (pinfunction "CFLY-_3") (pintype "unspecified"))
    )
    (net (code "31") (name "Net-(U3-EN)") (class "Default")
      (node (ref "R3") (pin "2") (pinfunction "2_2") (pintype "input"))
      (node (ref "U3") (pin "5") (pinfunction "EN_5") (pintype "unspecified"))
    )
    (net (code "32") (name "Net-(U6-A)") (class "Default")
      (node (ref "D4") (pin "1") (pinfunction "1_1") (pintype "unspecified"))
      (node (ref "R22") (pin "2") (pinfunction "2_2") (pintype "input"))
      (node (ref "U6") (pin "6") (pinfunction "A_6") (pintype "unspecified"))
    )
    (net (code "33") (name "Net-(U6-B)") (class "Default")
      (node (ref "D4") (pin "2") (pinfunction "2_2") (pintype "unspecified"))
      (node (ref "R20") (pin "2") (pinfunction "2_2") (pintype "input"))
      (node (ref "U6") (pin "7") (pinfunction "B_7") (pintype "unspecified"))
    )
    (net (code "34") (name "Net-(U10-P3.0{slash}RxD{slash}INT4#{slash}T2CLKO)") (class "Default")
      (node (ref "H1") (pin "2") (pinfunction "2_2") (pintype "unspecified"))
      (node (ref "U10") (pin "15") (pinfunction "P3.0/RxD/INT4#/T2CLKO_15") (pintype "input"))
    )
    (net (code "35") (name "Net-(U10-P3.1{slash}TxD{slash}T2)") (class "Default")
      (node (ref "H1") (pin "1") (pinfunction "1_1") (pintype "unspecified"))
      (node (ref "U10") (pin "16") (pinfunction "P3.1/TxD/T2_16") (pintype "input"))
    )
    (net (code "36") (name "Net-(U11A-IN1-)") (class "Default")
      (node (ref "C14") (pin "1") (pinfunction "1_1") (pintype "input"))
      (node (ref "R10") (pin "1") (pinfunction "1_1") (pintype "input"))
      (node (ref "R8") (pin "1") (pinfunction "1_1") (pintype "input"))
      (node (ref "U11") (pin "2") (pinfunction "IN1-_2") (pintype "unspecified"))
    )
    (net (code "37") (name "Net-(U11A-OUT1)") (class "Default")
      (node (ref "C14") (pin "2") (pinfunction "2_2") (pintype "input"))
      (node (ref "R4") (pin "2") (pinfunction "2_2") (pintype "input"))
      (node (ref "R8") (pin "2") (pinfunction "2_2") (pintype "input"))
      (node (ref "U11") (pin "1") (pinfunction "OUT1_1") (pintype "unspecified"))
    )
    (net (code "38") (name "Net-(U11B-IN2-)") (class "Default")
      (node (ref "C16") (pin "2") (pinfunction "2_2") (pintype "input"))
      (node (ref "R10") (pin "2") (pinfunction "2_2") (pintype "input"))
      (node (ref "R10") (pin "3") (pinfunction "3_3") (pintype "input"))
      (node (ref "R11") (pin "2") (pinfunction "2_2") (pintype "input"))
      (node (ref "U11") (pin "6") (pinfunction "IN2-_6") (pintype "unspecified"))
    )
    (net (code "39") (name "Net-(U11B-OUT2)") (class "Default")
      (node (ref "C16") (pin "1") (pinfunction "1_1") (pintype "input"))
      (node (ref "R11") (pin "1") (pinfunction "1_1") (pintype "input"))
      (node (ref "R12") (pin "2") (pinfunction "2_2") (pintype "input"))
      (node (ref "U11") (pin "7") (pinfunction "OUT2_7") (pintype "unspecified"))
    )
    (net (code "40") (name "Net-(U11C-IN3+)") (class "Default")
      (node (ref "R12") (pin "1") (pinfunction "1_1") (pintype "input"))
      (node (ref "R13") (pin "2") (pinfunction "2_2") (pintype "input"))
      (node (ref "U11") (pin "10") (pinfunction "IN3+_10") (pintype "unspecified"))
    )
    (net (code "41") (name "Net-(U11C-IN3-)") (class "Default")
      (node (ref "R4") (pin "1") (pinfunction "1_1") (pintype "input"))
      (node (ref "R5") (pin "2") (pinfunction "2_2") (pintype "input"))
      (node (ref "U11") (pin "9") (pinfunction "IN3-_9") (pintype "unspecified"))
    )
    (net (code "42") (name "Net-(U11D-IN4+)") (class "Default")
      (node (ref "R6") (pin "1") (pinfunction "1_1") (pintype "input"))
      (node (ref "R7") (pin "1") (pinfunction "1_1") (pintype "input"))
      (node (ref "U11") (pin "12") (pinfunction "IN4+_12") (pintype "unspecified"))
    )
    (net (code "43") (name "P12") (class "Default")
      (node (ref "R19") (pin "1") (pinfunction "1_1") (pintype "input"))
      (node (ref "U10") (pin "5") (pinfunction "ECI/SS/ADC2/P1.2_5") (pintype "input"))
      (node (ref "U6") (pin "2") (pinfunction "#RE_2") (pintype "unspecified"))
      (node (ref "U6") (pin "3") (pinfunction "DE_3") (pintype "unspecified"))
    )
    (net (code "44") (name "P20") (class "Default")
      (node (ref "C18") (pin "2") (pinfunction "2_2") (pintype "input"))
      (node (ref "R23") (pin "2") (pinfunction "2_2") (pintype "input"))
      (node (ref "U10") (pin "23") (pinfunction "P2.0/RSTOUT_LOW_23") (pintype "input"))
      (node (ref "U7") (pin "1") (pinfunction "G_1") (pintype "unspecified"))
    )
    (net (code "45") (name "P21") (class "Default")
      (node (ref "CN5") (pin "5") (pinfunction "5_5") (pintype "unspecified"))
      (node (ref "U10") (pin "24") (pinfunction "P2.1/SCLK_2_24") (pintype "input"))
    )
    (net (code "46") (name "P22") (class "Default")
      (node (ref "CN5") (pin "4") (pinfunction "4_4") (pintype "unspecified"))
      (node (ref "U10") (pin "25") (pinfunction "P2.2/MISO_2_25") (pintype "input"))
    )
    (net (code "47") (name "P23") (class "Default")
      (node (ref "CN5") (pin "3") (pinfunction "3_3") (pintype "unspecified"))
      (node (ref "U10") (pin "26") (pinfunction "P2.3/MOSI_2_26") (pintype "input"))
    )
    (net (code "48") (name "P24") (class "Default")
      (node (ref "CN5") (pin "2") (pinfunction "2_2") (pintype "unspecified"))
      (node (ref "U10") (pin "27") (pinfunction "P2.4/ECI_3/SS_2_27") (pintype "input"))
    )
    (net (code "49") (name "P25") (class "Default")
      (node (ref "C17") (pin "2") (pinfunction "2_2") (pintype "input"))
      (node (ref "R17") (pin "2") (pinfunction "2_2") (pintype "input"))
      (node (ref "U10") (pin "28") (pinfunction "P2.5/CCP0_3_28") (pintype "input"))
      (node (ref "U5") (pin "1") (pinfunction "G_1") (pintype "unspecified"))
    )
    (net (code "50") (name "P36") (class "Default")
      (node (ref "R26") (pin "1") (pinfunction "1_1") (pintype "input"))
      (node (ref "U10") (pin "21") (pinfunction "P3.6/INT2#/RxD_2/CCP1_2_21") (pintype "input"))
    )
    (net (code "51") (name "P37") (class "Default")
      (node (ref "R15") (pin "1") (pinfunction "1_1") (pintype "input"))
      (node (ref "U10") (pin "22") (pinfunction "P3.7/INT3#/TxD_2/CCP2/CCP2_2_22") (pintype "input"))
    )
    (net (code "52") (name "SCL") (class "Default")
      (node (ref "R28") (pin "2") (pinfunction "2_2") (pintype "input"))
      (node (ref "U10") (pin "2") (pinfunction "CCP2_3/P2.7_2") (pintype "input"))
      (node (ref "U9") (pin "6") (pinfunction "SCL_6") (pintype "unspecified"))
    )
    (net (code "53") (name "SDA") (class "Default")
      (node (ref "R29") (pin "2") (pinfunction "2_2") (pintype "input"))
      (node (ref "U10") (pin "1") (pinfunction "CCP1_3/P2.6_1") (pintype "input"))
      (node (ref "U9") (pin "5") (pinfunction "SDA_5") (pintype "unspecified"))
    )
    (net (code "54") (name "SN+") (class "Default")
      (node (ref "CN4") (pin "2") (pinfunction "2_2") (pintype "unspecified"))
      (node (ref "U11") (pin "3") (pinfunction "IN1+_3") (pintype "unspecified"))
    )
    (net (code "55") (name "SN-") (class "Default")
      (node (ref "CN4") (pin "1") (pinfunction "1_1") (pintype "unspecified"))
      (node (ref "U11") (pin "5") (pinfunction "IN2+_5") (pintype "unspecified"))
    )
    (net (code "56") (name "VBAT") (class "Default")
      (node (ref "C1") (pin "1") (pinfunction "1_1") (pintype "input"))
      (node (ref "CN4") (pin "4") (pinfunction "4_4") (pintype "unspecified"))
      (node (ref "R6") (pin "2") (pinfunction "2_2") (pintype "input"))
      (node (ref "SW1") (pin "2") (pinfunction "2_2") (pintype "unspecified"))
      (node (ref "U1") (pin "1") (pinfunction "VIN_1") (pintype "input"))
    )
    (net (code "57") (name "VCC") (class "Default")
      (node (ref "C11") (pin "2") (pinfunction "2_2") (pintype "unspecified"))
      (node (ref "C12") (pin "2") (pinfunction "2_2") (pintype "input"))
      (node (ref "C15") (pin "1") (pinfunction "1_1") (pintype "input"))
      (node (ref "C17") (pin "1") (pinfunction "1_1") (pintype "input"))
      (node (ref "C18") (pin "1") (pinfunction "1_1") (pintype "input"))
      (node (ref "C2") (pin "2") (pinfunction "2_2") (pintype "input"))
      (node (ref "C20") (pin "2") (pinfunction "2_2") (pintype "input"))
      (node (ref "C21") (pin "1") (pinfunction "1_1") (pintype "input"))
      (node (ref "C23") (pin "2") (pinfunction "2_2") (pintype "input"))
      (node (ref "C3") (pin "2") (pinfunction "2_2") (pintype "input"))
      (node (ref "C4") (pin "1") (pinfunction "1_1") (pintype "input"))
      (node (ref "C5") (pin "1") (pinfunction "1_1") (pintype "unspecified"))
      (node (ref "C6") (pin "1") (pinfunction "1_1") (pintype "unspecified"))
      (node (ref "CN5") (pin "7") (pinfunction "7_7") (pintype "unspecified"))
      (node (ref "D1") (pin "1") (pinfunction "C_1") (pintype "unspecified"))
      (node (ref "H1") (pin "3") (pinfunction "3_3") (pintype "unspecified"))
      (node (ref "L1") (pin "1") (pinfunction "1_1") (pintype "unspecified"))
      (node (ref "LED1") (pin "1") (pinfunction "C_1") (pintype "input"))
      (node (ref "R17") (pin "1") (pinfunction "1_1") (pintype "input"))
      (node (ref "R18") (pin "2") (pinfunction "2_2") (pintype "input"))
      (node (ref "R21") (pin "2") (pinfunction "2_2") (pintype "input"))
      (node (ref "R23") (pin "1") (pinfunction "1_1") (pintype "input"))
      (node (ref "R28") (pin "1") (pinfunction "1_1") (pintype "input"))
      (node (ref "R29") (pin "1") (pinfunction "1_1") (pintype "input"))
      (node (ref "R3") (pin "1") (pinfunction "1_1") (pintype "input"))
      (node (ref "U1") (pin "4") (pinfunction "FEEDBACK_4") (pintype "input"))
      (node (ref "U10") (pin "12") (pinfunction "Vcc_12") (pintype "input"))
      (node (ref "U11") (pin "4") (pinfunction "VCC+_4") (pintype "unspecified"))
      (node (ref "U12") (pin "2") (pinfunction "VIN_2") (pintype "input"))
      (node (ref "U3") (pin "2") (pinfunction "IN_2") (pintype "unspecified"))
      (node (ref "U4") (pin "1") (pinfunction "1_1") (pintype "input"))
      (node (ref "U5") (pin "2") (pinfunction "S_2") (pintype "unspecified"))
      (node (ref "U6") (pin "8") (pinfunction "VCC_8") (pintype "unspecified"))
      (node (ref "U7") (pin "2") (pinfunction "S_2") (pintype "unspecified"))
      (node (ref "U8") (pin "1") (pinfunction "1_1") (pintype "input"))
      (node (ref "U9") (pin "8") (pinfunction "VCC_8") (pintype "unspecified"))
    )
    (net (code "58") (name "VEE") (class "Default")
      (node (ref "C13") (pin "2") (pinfunction "2_2") (pintype "input"))
      (node (ref "C8") (pin "2") (pinfunction "2_2") (pintype "unspecified"))
      (node (ref "U11") (pin "11") (pinfunction "VCC-_11") (pintype "unspecified"))
      (node (ref "U3") (pin "1") (pinfunction "OUT_1") (pintype "unspecified"))
    )
    (net (code "59") (name "VRM") (class "Default")
      (node (ref "C10") (pin "2") (pinfunction "2_2") (pintype "input"))
      (node (ref "C9") (pin "2") (pinfunction "2_2") (pintype "unspecified"))
      (node (ref "D3") (pin "1") (pinfunction "C_1") (pintype "unspecified"))
      (node (ref "D5") (pin "1") (pinfunction "C_1") (pintype "unspecified"))
      (node (ref "R14") (pin "1") (pinfunction "1_1") (pintype "input"))
      (node (ref "R2") (pin "2") (pinfunction "2_2") (pintype "input"))
      (node (ref "R24") (pin "2") (pinfunction "2_2") (pintype "input"))
      (node (ref "R25") (pin "1") (pinfunction "1_1") (pintype "input"))
      (node (ref "R9") (pin "2") (pinfunction "2_2") (pintype "input"))
      (node (ref "RELAY1") (pin "2") (pinfunction "2_2") (pintype "input"))
      (node (ref "RELAY2") (pin "2") (pinfunction "2_2") (pintype "input"))
      (node (ref "U12") (pin "4") (pinfunction "+Vo_4") (pintype "input"))
    )
    (net (code "60") (name "XTAL1") (class "Default")
      (node (ref "C19") (pin "1") (pinfunction "1_1") (pintype "input"))
      (node (ref "U10") (pin "10") (pinfunction "XTAL1/TxD_3/ADC7/P1.7_10") (pintype "input"))
      (node (ref "X1") (pin "2") (pinfunction "2_2") (pintype "unspecified"))
    )
    (net (code "61") (name "XTAL2") (class "Default")
      (node (ref "C22") (pin "1") (pinfunction "1_1") (pintype "input"))
      (node (ref "U10") (pin "9") (pinfunction "XTAL2/RxD_3/ADC6/P1.6_9") (pintype "input"))
      (node (ref "X1") (pin "1") (pinfunction "1_1") (pintype "unspecified"))
    )
    (net (code "62") (name "unconnected-(SW1-Pad3)") (class "Default")
      (node (ref "SW1") (pin "3") (pinfunction "3_3") (pintype "unspecified+no_connect"))
    )
    (net (code "63") (name "unconnected-(SW1-Pad4)") (class "Default")
      (node (ref "SW1") (pin "4") (pinfunction "4_4") (pintype "unspecified+no_connect"))
    )
    (net (code "64") (name "unconnected-(SW1-Pad5)") (class "Default")
      (node (ref "SW1") (pin "5") (pinfunction "5_5") (pintype "unspecified+no_connect"))
    )
    (net (code "65") (name "unconnected-(U10-MCLKO{slash}RST{slash}P5.4-Pad11)") (class "Default")
      (node (ref "U10") (pin "11") (pinfunction "MCLKO/RST/P5.4_11") (pintype "input+no_connect"))
    )
    (net (code "66") (name "unconnected-(U10-P3.2{slash}INT0-Pad17)") (class "Default")
      (node (ref "U10") (pin "17") (pinfunction "P3.2/INT0_17") (pintype "input+no_connect"))
    )
    (net (code "67") (name "unconnected-(U10-P3.3{slash}INT1-Pad18)") (class "Default")
      (node (ref "U10") (pin "18") (pinfunction "P3.3/INT1_18") (pintype "input+no_connect"))
    )
    (net (code "68") (name "unconnected-(U10-P3.4{slash}T0{slash}T1CLKO{slash}ECI_2-Pad19)") (class "Default")
      (node (ref "U10") (pin "19") (pinfunction "P3.4/T0/T1CLKO/ECI_2_19") (pintype "input+no_connect"))
    )
    (net (code "69") (name "unconnected-(U10-P3.5{slash}T1{slash}T0CLKO{slash}CCP0_2-Pad20)") (class "Default")
      (node (ref "U10") (pin "20") (pinfunction "P3.5/T1/T0CLKO/CCP0_2_20") (pintype "input+no_connect"))
    )
    (net (code "70") (name "unconnected-(U10-P5.5-Pad13)") (class "Default")
      (node (ref "U10") (pin "13") (pinfunction "P5.5_13") (pintype "input+no_connect"))
    )
    (net (code "71") (name "unconnected-(U10-SCLK{slash}ADC5{slash}P1.5-Pad8)") (class "Default")
      (node (ref "U10") (pin "8") (pinfunction "SCLK/ADC5/P1.5_8") (pintype "input+no_connect"))
    )
  )
)
